# SNR8016VR-M.net
KiCad netlist of a schematic drawn in Altium Designer
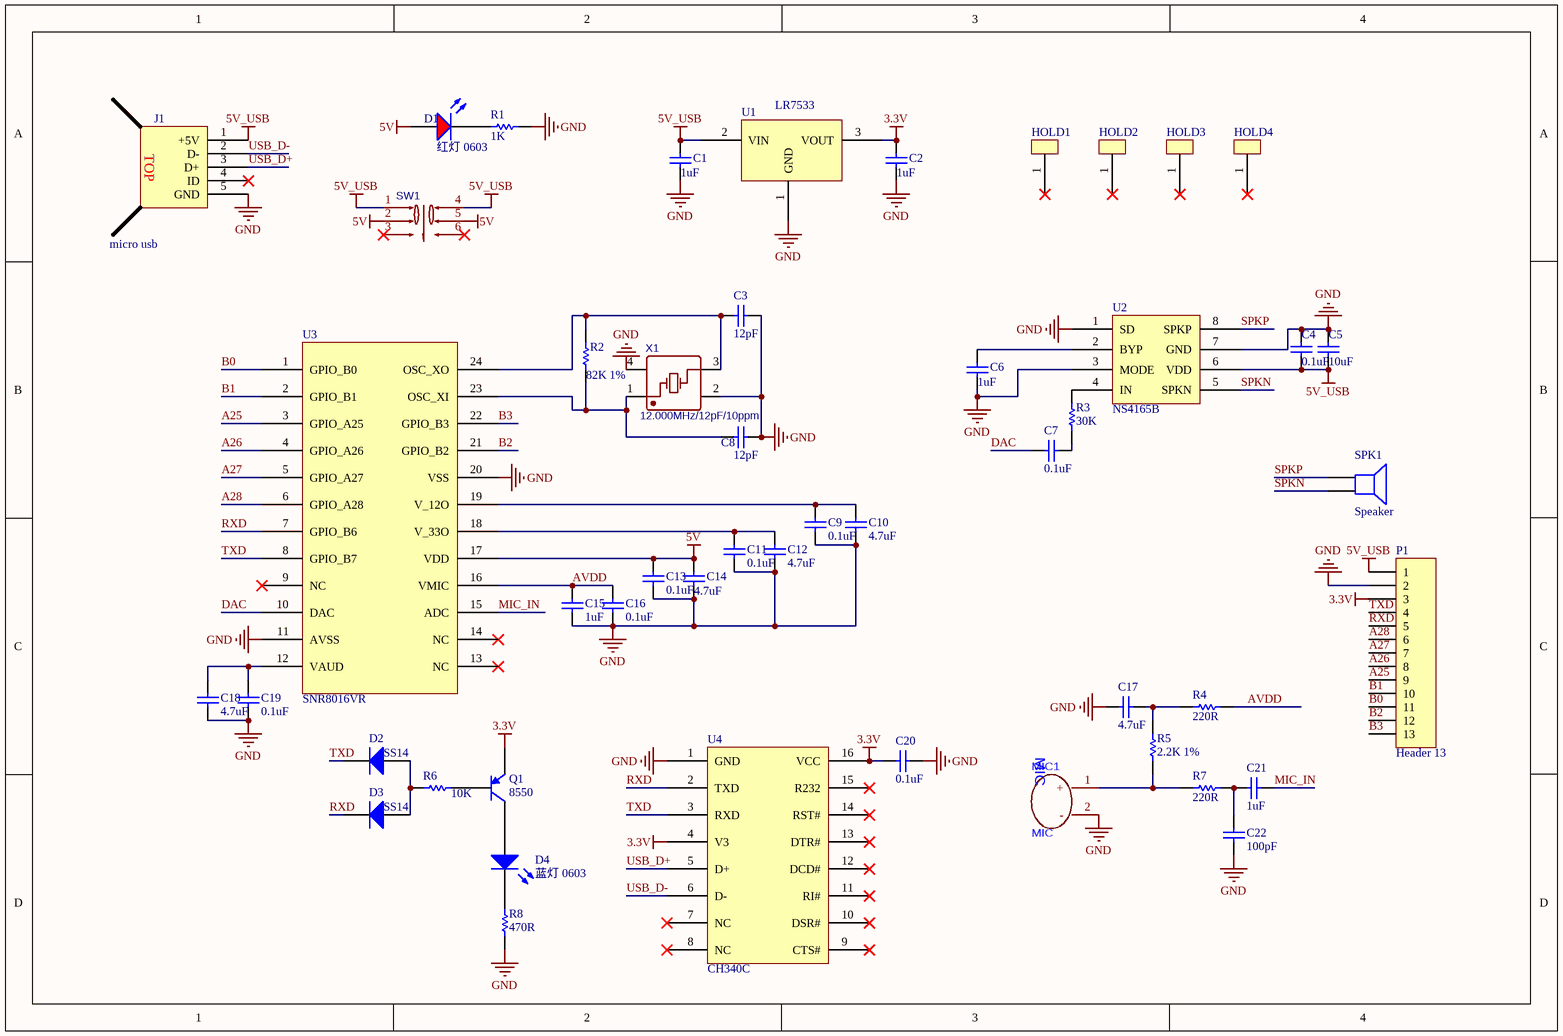
[diagram p0: SNR8016VR-M.SchDoc]

(export (version "E")
  (design (tool "Eeschema 10.0.6"))
  (components
    (comp (ref "C1")
      (value "1uF")
      (footprint "C0603_small")
      (description "Capacitor")
      (fields (field (name "Comment") "Cap") (field (name "PUBLISHER") "Altium Limited"))
      (libsource (lib "Miscellaneous Devices") (part "Cap"))
    )
    (comp (ref "C2")
      (value "1uF")
      (footprint "C0603_small")
      (description "Capacitor")
      (fields (field (name "Comment") "Cap") (field (name "PUBLISHER") "Altium Limited"))
      (libsource (lib "Miscellaneous Devices") (part "Cap"))
    )
    (comp (ref "C3")
      (value "12pF")
      (footprint "C0603_small")
      (description "Capacitor")
      (fields (field (name "Comment") "Cap") (field (name "PUBLISHER") "Altium Limited"))
      (libsource (lib "Miscellaneous Devices") (part "Cap"))
    )
    (comp (ref "C4")
      (value "0.1uF")
      (footprint "C0603_small")
      (description "Capacitor")
      (fields (field (name "Comment") "Cap") (field (name "PUBLISHER") "Altium Limited"))
      (libsource (lib "Miscellaneous Devices") (part "Cap"))
    )
    (comp (ref "C5")
      (value "10uF")
      (footprint "C0603_small")
      (description "Capacitor")
      (fields (field (name "Comment") "Cap") (field (name "PUBLISHER") "Altium Limited"))
      (libsource (lib "Miscellaneous Devices") (part "Cap"))
    )
    (comp (ref "C6")
      (value "1uF")
      (footprint "C0603_small")
      (description "Capacitor")
      (fields (field (name "Comment") "Cap") (field (name "PUBLISHER") "Altium Limited"))
      (libsource (lib "Miscellaneous Devices") (part "Cap"))
    )
    (comp (ref "C7")
      (value "0.1uF")
      (footprint "C0603_small")
      (description "Capacitor")
      (fields (field (name "Comment") "Cap") (field (name "PUBLISHER") "Altium Limited"))
      (libsource (lib "Miscellaneous Devices") (part "Cap"))
    )
    (comp (ref "C8")
      (value "12pF")
      (footprint "C0603_small")
      (description "Capacitor")
      (fields (field (name "Comment") "Cap") (field (name "PUBLISHER") "Altium Limited"))
      (libsource (lib "Miscellaneous Devices") (part "Cap"))
    )
    (comp (ref "C9")
      (value "0.1uF")
      (footprint "C0603_small")
      (description "Capacitor")
      (fields (field (name "Comment") "Cap") (field (name "PUBLISHER") "Altium Limited"))
      (libsource (lib "Miscellaneous Devices") (part "Cap"))
    )
    (comp (ref "C10")
      (value "4.7uF")
      (footprint "C0603_small")
      (description "Capacitor")
      (fields (field (name "Comment") "Cap") (field (name "PUBLISHER") "Altium Limited"))
      (libsource (lib "Miscellaneous Devices") (part "Cap"))
    )
    (comp (ref "C11")
      (value "0.1uF")
      (footprint "C0603_small")
      (description "Capacitor")
      (fields (field (name "Comment") "Cap") (field (name "PUBLISHER") "Altium Limited"))
      (libsource (lib "Miscellaneous Devices") (part "Cap"))
    )
    (comp (ref "C12")
      (value "4.7uF")
      (footprint "C0603_small")
      (description "Capacitor")
      (fields (field (name "Comment") "Cap") (field (name "PUBLISHER") "Altium Limited"))
      (libsource (lib "Miscellaneous Devices") (part "Cap"))
    )
    (comp (ref "C13")
      (value "0.1uF")
      (footprint "C0603_small")
      (description "Capacitor")
      (fields (field (name "Comment") "Cap") (field (name "PUBLISHER") "Altium Limited"))
      (libsource (lib "Miscellaneous Devices") (part "Cap"))
    )
    (comp (ref "C14")
      (value "4.7uF")
      (footprint "C0603_small")
      (description "Capacitor")
      (fields (field (name "Comment") "Cap") (field (name "PUBLISHER") "Altium Limited"))
      (libsource (lib "Miscellaneous Devices") (part "Cap"))
    )
    (comp (ref "C15")
      (value "1uF")
      (footprint "C0603_small")
      (description "Capacitor")
      (fields (field (name "Comment") "Cap") (field (name "PUBLISHER") "Altium Limited"))
      (libsource (lib "Miscellaneous Devices") (part "Cap"))
    )
    (comp (ref "C16")
      (value "0.1uF")
      (footprint "C0603_small")
      (description "Capacitor")
      (fields (field (name "Comment") "Cap") (field (name "PUBLISHER") "Altium Limited"))
      (libsource (lib "Miscellaneous Devices") (part "Cap"))
    )
    (comp (ref "C17")
      (value "4.7uF")
      (footprint "C0603_small")
      (description "贴片电容")
      (libsource (lib "Cap") (part "0603 1uF (105) 10% 50V"))
    )
    (comp (ref "C18")
      (value "4.7uF")
      (footprint "C0603_small")
      (description "Capacitor")
      (fields (field (name "Comment") "Cap") (field (name "PUBLISHER") "Altium Limited"))
      (libsource (lib "Miscellaneous Devices") (part "Cap"))
    )
    (comp (ref "C19")
      (value "0.1uF")
      (footprint "C0603_small")
      (description "Capacitor")
      (fields (field (name "Comment") "Cap") (field (name "PUBLISHER") "Altium Limited"))
      (libsource (lib "Miscellaneous Devices") (part "Cap"))
    )
    (comp (ref "C20")
      (value "0.1uF")
      (footprint "C0603_small")
      (description "Capacitor")
      (fields (field (name "Comment") "Cap") (field (name "PUBLISHER") "Altium Limited"))
      (libsource (lib "Miscellaneous Devices") (part "Cap"))
    )
    (comp (ref "C21")
      (value "1uF")
      (footprint "C0603_small")
      (description "贴片电容")
      (libsource (lib "Cap") (part "0402 2.7pF (2R7) 0.25pF 50V"))
    )
    (comp (ref "C22")
      (value "100pF")
      (footprint "C0603_small")
      (description "贴片电容")
      (libsource (lib "Cap") (part "0402 2.7pF (2R7) 0.25pF 50V"))
    )
    (comp (ref "D1")
      (value "红灯 0603")
      (footprint "0603_LED_S1")
      (description "发光二极管")
      (libsource (lib "LED") (part "0603 红灯"))
    )
    (comp (ref "D2")
      (value "SS14")
      (footprint "SOD-123")
      (description "Default Diode")
      (fields (field (name "PUBLISHER") "Altium Limited"))
      (libsource (lib "Miscellaneous Devices") (part "Diode"))
    )
    (comp (ref "D3")
      (value "SS14")
      (footprint "SOD-123")
      (description "Default Diode")
      (fields (field (name "PUBLISHER") "Altium Limited"))
      (libsource (lib "Miscellaneous Devices") (part "Diode"))
    )
    (comp (ref "D4")
      (value "蓝灯 0603")
      (footprint "0603_LED_S1")
      (description "发光二极管")
      (libsource (lib "LED") (part "0603 蓝灯"))
    )
    (comp (ref "HOLD1")
      (value "TEST POINT")
      (footprint "HOLD330-600")
      (libsource (lib "SNANER—SCH库") (part "TEST POINT"))
    )
    (comp (ref "HOLD2")
      (value "TEST POINT")
      (footprint "HOLD330-600")
      (libsource (lib "SNANER—SCH库") (part "TEST POINT"))
    )
    (comp (ref "HOLD3")
      (value "TEST POINT")
      (footprint "HOLD330-600")
      (libsource (lib "SNANER—SCH库") (part "TEST POINT"))
    )
    (comp (ref "HOLD4")
      (value "TEST POINT")
      (footprint "HOLD330-600")
      (libsource (lib "SNANER—SCH库") (part "TEST POINT"))
    )
    (comp (ref "J1")
      (value "micro usb")
      (footprint "MICRO-USB-SMD_5P-P0.65-H-M_MICRO-USB-5P")
      (libsource (lib "SNANER—SCH库") (part "micro usb"))
    )
    (comp (ref "MIC1") (value "MIC") (footprint "MIC_9767") (libsource (lib "SNANER—SCH库") (part "MIC")))
    (comp (ref "P1")
      (value "Header 13")
      (footprint "Header 1*13P 2.54mm")
      (description "Header, 13-Pin")
      (fields (field (name "PUBLISHER") "Altium Limited"))
      (libsource (lib "Miscellaneous Connectors") (part "Header 13"))
    )
    (comp (ref "Q1")
      (value "8550")
      (footprint "SOT-23 - PNP")
      (description "PNP Bipolar Transistor")
      (fields (field (name "PUBLISHER") "Altium Limited"))
      (libsource (lib "Miscellaneous Devices") (part "PNP"))
    )
    (comp (ref "R1")
      (value "1K")
      (footprint "R0603_small")
      (description "Resistor")
      (fields (field (name "Comment") "Res1") (field (name "PUBLISHER") "Altium Limited"))
      (libsource (lib "Miscellaneous Devices") (part "Res1"))
    )
    (comp (ref "R2")
      (value "82K 1%")
      (footprint "R0603_small")
      (description "Resistor")
      (fields (field (name "Comment") "Res1") (field (name "PUBLISHER") "Altium Limited"))
      (libsource (lib "Miscellaneous Devices") (part "Res1"))
    )
    (comp (ref "R3")
      (value "30K")
      (footprint "R0603_small")
      (description "Resistor")
      (fields (field (name "Comment") "Res1") (field (name "PUBLISHER") "Altium Limited"))
      (libsource (lib "Miscellaneous Devices") (part "Res1"))
    )
    (comp (ref "R4")
      (value "220R")
      (footprint "R0603_small")
      (description "Resistor")
      (fields (field (name "Comment") "Res1") (field (name "PUBLISHER") "Altium Limited"))
      (libsource (lib "Miscellaneous Devices") (part "Res1"))
    )
    (comp (ref "R5")
      (value "2.2K 1%")
      (footprint "R0603_small")
      (description "Resistor")
      (fields (field (name "Comment") "Res1") (field (name "PUBLISHER") "Altium Limited"))
      (libsource (lib "Miscellaneous Devices") (part "Res1"))
    )
    (comp (ref "R6")
      (value "10K")
      (footprint "R0603_small")
      (description "Resistor")
      (fields (field (name "Comment") "Res1") (field (name "PUBLISHER") "Altium Limited"))
      (libsource (lib "Miscellaneous Devices") (part "Res1"))
    )
    (comp (ref "R7")
      (value "220R")
      (footprint "R0603_small")
      (description "Resistor")
      (fields (field (name "Comment") "Res1") (field (name "PUBLISHER") "Altium Limited"))
      (libsource (lib "Miscellaneous Devices") (part "Res1"))
    )
    (comp (ref "R8")
      (value "470R")
      (footprint "R0603_small")
      (description "Resistor")
      (fields (field (name "Comment") "Res1") (field (name "PUBLISHER") "Altium Limited"))
      (libsource (lib "Miscellaneous Devices") (part "Res1"))
    )
    (comp (ref "SPK1")
      (value "Speaker")
      (footprint "SPEAKER_2308")
      (description "Loudspeaker")
      (fields (field (name "PUBLISHER") "Altium Limited"))
      (libsource (lib "Miscellaneous Devices") (part "Speaker"))
    )
    (comp (ref "SW1")
      (value "SW_XKB5858-W-TP")
      (footprint "SW-SMD_6P-L5.8-W5.8-P2.00-LS8.3")
      (fields
        (field (name "BOM_SUPPLIER PART") "C381091")
        (field (name "BOM_MANUFACTURER PART") "XKB5858-W-TP")
        (field (name "CONTRIBUTOR") "LCSC")
      )
      (libsource (lib "SNANER—SCH库") (part "SW_XKB5858-W-TP"))
    )
    (comp (ref "U1") (value "LR7533") (footprint "SOT-89") (libsource (lib "SNANER—SCH库") (part "LR7533")))
    (comp (ref "U2") (value "NS4165B") (footprint "NS4165") (libsource (lib "SNANER—SCH库") (part "NS4165")))
    (comp (ref "U3")
      (value "SNR8016VR")
      (footprint "QSOP-24_L8.7-W4.0-P0.65-LS6.0-BL")
      (libsource (lib "SNANER—SCH库") (part "SNR8016VR"))
    )
    (comp (ref "U4")
      (value "CH340C")
      (footprint "SOP-16_150mil")
      (libsource (lib "SNANER—SCH库") (part "CH340C"))
    )
    (comp (ref "X1")
      (value "12.000MHz/12pF/10ppm")
      (footprint "CY3225-4")
      (fields
        (field (name "BOM_SUPPLIER PART") "C362472")
        (field (name "BOM_MANUFACTURER PART") "SMD-3225_4P 12.288MHZ 12PF")
        (field (name "CONTRIBUTOR") "LCSC")
      )
      (libsource (lib "SNANER—SCH库") (part "12.000MHz"))
    )
  )
  (nets
    (net (code "1") (name "/A25") (class "Default")
      (node (ref "P1") (pin "9") (pinfunction "9_9") (pintype "passive"))
      (node (ref "U3") (pin "3") (pinfunction "GPIO_A25_3") (pintype "passive"))
    )
    (net (code "2") (name "/A26") (class "Default")
      (node (ref "P1") (pin "8") (pinfunction "8_8") (pintype "passive"))
      (node (ref "U3") (pin "4") (pinfunction "GPIO_A26_4") (pintype "passive"))
    )
    (net (code "3") (name "/A27") (class "Default")
      (node (ref "P1") (pin "7") (pinfunction "7_7") (pintype "passive"))
      (node (ref "U3") (pin "5") (pinfunction "GPIO_A27_5") (pintype "passive"))
    )
    (net (code "4") (name "/A28") (class "Default")
      (node (ref "P1") (pin "6") (pinfunction "6_6") (pintype "passive"))
      (node (ref "U3") (pin "6") (pinfunction "GPIO_A28_6") (pintype "passive"))
    )
    (net (code "5") (name "/AVDD") (class "Default")
      (node (ref "C15") (pin "2") (pinfunction "2_2") (pintype "passive"))
      (node (ref "C16") (pin "2") (pinfunction "2_2") (pintype "passive"))
      (node (ref "R4") (pin "1") (pinfunction "1_1") (pintype "passive"))
      (node (ref "U3") (pin "16") (pinfunction "VMIC_16") (pintype "passive"))
    )
    (net (code "6") (name "/B0") (class "Default")
      (node (ref "P1") (pin "11") (pinfunction "11_11") (pintype "passive"))
      (node (ref "U3") (pin "1") (pinfunction "GPIO_B0_1") (pintype "passive"))
    )
    (net (code "7") (name "/B1") (class "Default")
      (node (ref "P1") (pin "10") (pinfunction "10_10") (pintype "passive"))
      (node (ref "U3") (pin "2") (pinfunction "GPIO_B1_2") (pintype "passive"))
    )
    (net (code "8") (name "/B2") (class "Default")
      (node (ref "P1") (pin "12") (pinfunction "12_12") (pintype "passive"))
      (node (ref "U3") (pin "21") (pinfunction "GPIO_B2_21") (pintype "passive"))
    )
    (net (code "9") (name "/B3") (class "Default")
      (node (ref "P1") (pin "13") (pinfunction "13_13") (pintype "passive"))
      (node (ref "U3") (pin "22") (pinfunction "GPIO_B3_22") (pintype "passive"))
    )
    (net (code "10") (name "/DAC") (class "Default")
      (node (ref "C7") (pin "1") (pinfunction "1_1") (pintype "passive"))
      (node (ref "U3") (pin "10") (pinfunction "DAC_10") (pintype "passive"))
    )
    (net (code "11") (name "/MIC_IN") (class "Default")
      (node (ref "C21") (pin "1") (pinfunction "1_1") (pintype "passive"))
      (node (ref "U3") (pin "15") (pinfunction "ADC_15") (pintype "passive"))
    )
    (net (code "12") (name "/RXD") (class "Default")
      (node (ref "D3") (pin "2") (pinfunction "K_2") (pintype "passive"))
      (node (ref "P1") (pin "5") (pinfunction "5_5") (pintype "passive"))
      (node (ref "U3") (pin "7") (pinfunction "GPIO_B6_7") (pintype "passive"))
      (node (ref "U4") (pin "2") (pinfunction "TXD_2") (pintype "passive"))
    )
    (net (code "13") (name "/SPKN") (class "Default")
      (node (ref "SPK1") (pin "2") (pinfunction "2_2") (pintype "passive"))
      (node (ref "U2") (pin "5") (pinfunction "SPKN_5") (pintype "passive"))
    )
    (net (code "14") (name "/SPKP") (class "Default")
      (node (ref "SPK1") (pin "1") (pinfunction "1_1") (pintype "passive"))
      (node (ref "U2") (pin "8") (pinfunction "SPKP_8") (pintype "passive"))
    )
    (net (code "15") (name "/TXD") (class "Default")
      (node (ref "D2") (pin "2") (pinfunction "K_2") (pintype "passive"))
      (node (ref "P1") (pin "4") (pinfunction "4_4") (pintype "passive"))
      (node (ref "U3") (pin "8") (pinfunction "GPIO_B7_8") (pintype "passive"))
      (node (ref "U4") (pin "3") (pinfunction "RXD_3") (pintype "passive"))
    )
    (net (code "16") (name "/USB_D+") (class "Default")
      (node (ref "J1") (pin "3") (pinfunction "D+_3") (pintype "passive"))
      (node (ref "U4") (pin "5") (pinfunction "D+_5") (pintype "passive"))
    )
    (net (code "17") (name "/USB_D-") (class "Default")
      (node (ref "J1") (pin "2") (pinfunction "D-_2") (pintype "passive"))
      (node (ref "U4") (pin "6") (pinfunction "D-_6") (pintype "passive"))
    )
    (net (code "18") (name "3.3V") (class "Default")
      (node (ref "C2") (pin "2") (pinfunction "2_2") (pintype "passive"))
      (node (ref "C20") (pin "2") (pinfunction "2_2") (pintype "passive"))
      (node (ref "P1") (pin "3") (pinfunction "3_3") (pintype "passive"))
      (node (ref "Q1") (pin "3") (pinfunction "E_3") (pintype "passive"))
      (node (ref "U1") (pin "3") (pinfunction "VOUT_3") (pintype "passive"))
      (node (ref "U4") (pin "16") (pinfunction "VCC_16") (pintype "passive"))
      (node (ref "U4") (pin "4") (pinfunction "V3_4") (pintype "passive"))
    )
    (net (code "19") (name "5V") (class "Default")
      (node (ref "C13") (pin "2") (pinfunction "2_2") (pintype "passive"))
      (node (ref "C14") (pin "2") (pinfunction "2_2") (pintype "passive"))
      (node (ref "D1") (pin "A") (pinfunction "A_A") (pintype "passive"))
      (node (ref "SW1") (pin "2") (pinfunction "2_2") (pintype "passive"))
      (node (ref "SW1") (pin "5") (pinfunction "5_5") (pintype "passive"))
      (node (ref "U3") (pin "17") (pinfunction "VDD_17") (pintype "passive"))
    )
    (net (code "20") (name "5V_USB") (class "Default")
      (node (ref "C1") (pin "2") (pinfunction "2_2") (pintype "passive"))
      (node (ref "C4") (pin "2") (pinfunction "2_2") (pintype "passive"))
      (node (ref "C5") (pin "1") (pinfunction "1_1") (pintype "passive"))
      (node (ref "J1") (pin "1") (pinfunction "+5V_1") (pintype "passive"))
      (node (ref "P1") (pin "1") (pinfunction "1_1") (pintype "passive"))
      (node (ref "SW1") (pin "1") (pinfunction "1_1") (pintype "passive"))
      (node (ref "SW1") (pin "4") (pinfunction "4_4") (pintype "passive"))
      (node (ref "U1") (pin "2") (pinfunction "VIN_2") (pintype "passive"))
      (node (ref "U2") (pin "6") (pinfunction "VDD_6") (pintype "passive"))
    )
    (net (code "21") (name "GND") (class "Default")
      (node (ref "C1") (pin "1") (pinfunction "1_1") (pintype "passive"))
      (node (ref "C10") (pin "1") (pinfunction "1_1") (pintype "passive"))
      (node (ref "C11") (pin "1") (pinfunction "1_1") (pintype "passive"))
      (node (ref "C12") (pin "1") (pinfunction "1_1") (pintype "passive"))
      (node (ref "C13") (pin "1") (pinfunction "1_1") (pintype "passive"))
      (node (ref "C14") (pin "1") (pinfunction "1_1") (pintype "passive"))
      (node (ref "C15") (pin "1") (pinfunction "1_1") (pintype "passive"))
      (node (ref "C16") (pin "1") (pinfunction "1_1") (pintype "passive"))
      (node (ref "C17") (pin "2") (pinfunction "2_2") (pintype "passive"))
      (node (ref "C18") (pin "1") (pinfunction "1_1") (pintype "passive"))
      (node (ref "C19") (pin "1") (pinfunction "1_1") (pintype "passive"))
      (node (ref "C2") (pin "1") (pinfunction "1_1") (pintype "passive"))
      (node (ref "C20") (pin "1") (pinfunction "1_1") (pintype "passive"))
      (node (ref "C22") (pin "1") (pinfunction "1_1") (pintype "passive"))
      (node (ref "C3") (pin "1") (pinfunction "1_1") (pintype "passive"))
      (node (ref "C4") (pin "1") (pinfunction "1_1") (pintype "passive"))
      (node (ref "C5") (pin "2") (pinfunction "2_2") (pintype "passive"))
      (node (ref "C6") (pin "1") (pinfunction "1_1") (pintype "passive"))
      (node (ref "C8") (pin "1") (pinfunction "1_1") (pintype "passive"))
      (node (ref "C9") (pin "1") (pinfunction "1_1") (pintype "passive"))
      (node (ref "J1") (pin "5") (pinfunction "GND_5") (pintype "passive"))
      (node (ref "MIC1") (pin "2") (pinfunction "-_2") (pintype "passive"))
      (node (ref "P1") (pin "2") (pinfunction "2_2") (pintype "passive"))
      (node (ref "R1") (pin "2") (pinfunction "2_2") (pintype "passive"))
      (node (ref "R8") (pin "1") (pinfunction "1_1") (pintype "passive"))
      (node (ref "U1") (pin "1") (pinfunction "GND_1") (pintype "passive"))
      (node (ref "U2") (pin "1") (pinfunction "SD_1") (pintype "passive"))
      (node (ref "U2") (pin "3") (pinfunction "MODE_3") (pintype "passive"))
      (node (ref "U2") (pin "7") (pinfunction "GND_7") (pintype "passive"))
      (node (ref "U3") (pin "11") (pinfunction "AVSS_11") (pintype "passive"))
      (node (ref "U3") (pin "20") (pinfunction "VSS_20") (pintype "passive"))
      (node (ref "U4") (pin "1") (pinfunction "GND_1") (pintype "passive"))
      (node (ref "X1") (pin "2") (pinfunction "GND_2") (pintype "passive"))
      (node (ref "X1") (pin "4") (pinfunction "GND_4") (pintype "passive"))
    )
    (net (code "22") (name "Net-(C7-Pad2)") (class "Default")
      (node (ref "C7") (pin "2") (pinfunction "2_2") (pintype "passive"))
      (node (ref "R3") (pin "2") (pinfunction "2_2") (pintype "passive"))
    )
    (net (code "23") (name "Net-(C17-Pad1)") (class "Default")
      (node (ref "C17") (pin "1") (pinfunction "1_1") (pintype "passive"))
      (node (ref "R4") (pin "2") (pinfunction "2_2") (pintype "passive"))
      (node (ref "R5") (pin "1") (pinfunction "1_1") (pintype "passive"))
    )
    (net (code "24") (name "Net-(C21-Pad2)") (class "Default")
      (node (ref "C21") (pin "2") (pinfunction "2_2") (pintype "passive"))
      (node (ref "C22") (pin "2") (pinfunction "2_2") (pintype "passive"))
      (node (ref "R7") (pin "1") (pinfunction "1_1") (pintype "passive"))
    )
    (net (code "25") (name "Net-(D1-PadK)") (class "Default")
      (node (ref "D1") (pin "K") (pinfunction "K_K") (pintype "passive"))
      (node (ref "R1") (pin "1") (pinfunction "1_1") (pintype "passive"))
    )
    (net (code "26") (name "Net-(D2-A)") (class "Default")
      (node (ref "D2") (pin "1") (pinfunction "A_1") (pintype "passive"))
      (node (ref "D3") (pin "1") (pinfunction "A_1") (pintype "passive"))
      (node (ref "R6") (pin "1") (pinfunction "1_1") (pintype "passive"))
    )
    (net (code "27") (name "Net-(D4-PadK)") (class "Default")
      (node (ref "D4") (pin "K") (pinfunction "K_K") (pintype "passive"))
      (node (ref "R8") (pin "2") (pinfunction "2_2") (pintype "passive"))
    )
    (net (code "28") (name "Net-(MIC1-+)") (class "Default")
      (node (ref "MIC1") (pin "1") (pinfunction "+_1") (pintype "passive"))
      (node (ref "R5") (pin "2") (pinfunction "2_2") (pintype "passive"))
      (node (ref "R7") (pin "2") (pinfunction "2_2") (pintype "passive"))
    )
    (net (code "29") (name "Net-(Q1-B)") (class "Default")
      (node (ref "Q1") (pin "2") (pinfunction "B_2") (pintype "passive"))
      (node (ref "R6") (pin "2") (pinfunction "2_2") (pintype "passive"))
    )
    (net (code "30") (name "Net-(Q1-C)") (class "Default")
      (node (ref "D4") (pin "A") (pinfunction "A_A") (pintype "passive"))
      (node (ref "Q1") (pin "1") (pinfunction "C_1") (pintype "passive"))
    )
    (net (code "31") (name "Net-(U2-BYP)") (class "Default")
      (node (ref "C6") (pin "2") (pinfunction "2_2") (pintype "passive"))
      (node (ref "U2") (pin "2") (pinfunction "BYP_2") (pintype "passive"))
    )
    (net (code "32") (name "Net-(U2-IN)") (class "Default")
      (node (ref "R3") (pin "1") (pinfunction "1_1") (pintype "passive"))
      (node (ref "U2") (pin "4") (pinfunction "IN_4") (pintype "passive"))
    )
    (net (code "33") (name "Net-(U3-OSC_XI)") (class "Default")
      (node (ref "C8") (pin "2") (pinfunction "2_2") (pintype "passive"))
      (node (ref "R2") (pin "1") (pinfunction "1_1") (pintype "passive"))
      (node (ref "U3") (pin "23") (pinfunction "OSC_XI_23") (pintype "passive"))
      (node (ref "X1") (pin "1") (pinfunction "OE#_1") (pintype "passive"))
    )
    (net (code "34") (name "Net-(U3-OSC_XO)") (class "Default")
      (node (ref "C3") (pin "2") (pinfunction "2_2") (pintype "passive"))
      (node (ref "R2") (pin "2") (pinfunction "2_2") (pintype "passive"))
      (node (ref "U3") (pin "24") (pinfunction "OSC_XO_24") (pintype "passive"))
      (node (ref "X1") (pin "3") (pinfunction "OUT_3") (pintype "passive"))
    )
    (net (code "35") (name "Net-(U3-VAUD)") (class "Default")
      (node (ref "C18") (pin "2") (pinfunction "2_2") (pintype "passive"))
      (node (ref "C19") (pin "2") (pinfunction "2_2") (pintype "passive"))
      (node (ref "U3") (pin "12") (pinfunction "VAUD_12") (pintype "passive"))
    )
    (net (code "36") (name "Net-(U3-V_12O)") (class "Default")
      (node (ref "C10") (pin "2") (pinfunction "2_2") (pintype "passive"))
      (node (ref "C9") (pin "2") (pinfunction "2_2") (pintype "passive"))
      (node (ref "U3") (pin "19") (pinfunction "V_12O_19") (pintype "passive"))
    )
    (net (code "37") (name "Net-(U3-V_33O)") (class "Default")
      (node (ref "C11") (pin "2") (pinfunction "2_2") (pintype "passive"))
      (node (ref "C12") (pin "2") (pinfunction "2_2") (pintype "passive"))
      (node (ref "U3") (pin "18") (pinfunction "V_33O_18") (pintype "passive"))
    )
    (net (code "38") (name "unconnected-(HOLD1-VOUT-Pad1)") (class "Default")
      (node (ref "HOLD1") (pin "1") (pinfunction "VOUT_1") (pintype "passive+no_connect"))
    )
    (net (code "39") (name "unconnected-(HOLD2-VOUT-Pad1)") (class "Default")
      (node (ref "HOLD2") (pin "1") (pinfunction "VOUT_1") (pintype "passive+no_connect"))
    )
    (net (code "40") (name "unconnected-(HOLD3-VOUT-Pad1)") (class "Default")
      (node (ref "HOLD3") (pin "1") (pinfunction "VOUT_1") (pintype "passive+no_connect"))
    )
    (net (code "41") (name "unconnected-(HOLD4-VOUT-Pad1)") (class "Default")
      (node (ref "HOLD4") (pin "1") (pinfunction "VOUT_1") (pintype "passive+no_connect"))
    )
    (net (code "42") (name "unconnected-(J1-ID-Pad4)") (class "Default")
      (node (ref "J1") (pin "4") (pinfunction "ID_4") (pintype "passive+no_connect"))
    )
    (net (code "43") (name "unconnected-(SW1-Pad3)") (class "Default")
      (node (ref "SW1") (pin "3") (pinfunction "3_3") (pintype "passive+no_connect"))
    )
    (net (code "44") (name "unconnected-(SW1-Pad6)") (class "Default")
      (node (ref "SW1") (pin "6") (pinfunction "6_6") (pintype "passive+no_connect"))
    )
    (net (code "45") (name "unconnected-(U3-NC-Pad9)") (class "Default")
      (node (ref "U3") (pin "9") (pinfunction "NC_9") (pintype "passive+no_connect"))
    )
    (net (code "46") (name "unconnected-(U3-NC-Pad13)") (class "Default")
      (node (ref "U3") (pin "13") (pinfunction "NC_13") (pintype "passive+no_connect"))
    )
    (net (code "47") (name "unconnected-(U3-NC-Pad14)") (class "Default")
      (node (ref "U3") (pin "14") (pinfunction "NC_14") (pintype "passive+no_connect"))
    )
    (net (code "48") (name "unconnected-(U4-CTS#-Pad9)") (class "Default")
      (node (ref "U4") (pin "9") (pinfunction "CTS#_9") (pintype "passive+no_connect"))
    )
    (net (code "49") (name "unconnected-(U4-DCD#-Pad12)") (class "Default")
      (node (ref "U4") (pin "12") (pinfunction "DCD#_12") (pintype "passive+no_connect"))
    )
    (net (code "50") (name "unconnected-(U4-DSR#-Pad10)") (class "Default")
      (node (ref "U4") (pin "10") (pinfunction "DSR#_10") (pintype "passive+no_connect"))
    )
    (net (code "51") (name "unconnected-(U4-DTR#-Pad13)") (class "Default")
      (node (ref "U4") (pin "13") (pinfunction "DTR#_13") (pintype "passive+no_connect"))
    )
    (net (code "52") (name "unconnected-(U4-NC-Pad7)") (class "Default")
      (node (ref "U4") (pin "7") (pinfunction "NC_7") (pintype "passive+no_connect"))
    )
    (net (code "53") (name "unconnected-(U4-NC-Pad8)") (class "Default")
      (node (ref "U4") (pin "8") (pinfunction "NC_8") (pintype "passive+no_connect"))
    )
    (net (code "54") (name "unconnected-(U4-R232-Pad15)") (class "Default")
      (node (ref "U4") (pin "15") (pinfunction "R232_15") (pintype "passive+no_connect"))
    )
    (net (code "55") (name "unconnected-(U4-RI#-Pad11)") (class "Default")
      (node (ref "U4") (pin "11") (pinfunction "RI#_11") (pintype "passive+no_connect"))
    )
    (net (code "56") (name "unconnected-(U4-RST#-Pad14)") (class "Default")
      (node (ref "U4") (pin "14") (pinfunction "RST#_14") (pintype "passive+no_connect"))
    )
  )
)
